# DRV8825.net
KiCad netlist of a schematic drawn in EAGLE
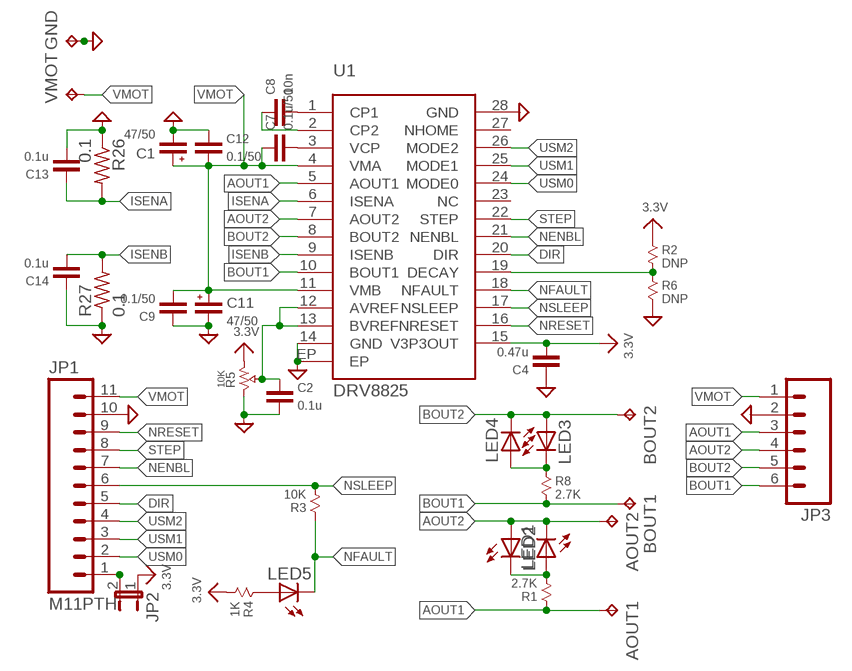
[diagram p0: schematic, sheet 1]

(export (version "E")
  (design (tool "Eeschema 10.0.6"))
  (components
    (comp (ref "AOUT1")
      (value "TPTP18R")
      (footprint "eagle-import:TP18R")
      (libsource (lib "eagle-import") (part "TPTP18R"))
    )
    (comp (ref "AOUT2")
      (value "TPTP18R")
      (footprint "eagle-import:TP18R")
      (libsource (lib "eagle-import") (part "TPTP18R"))
    )
    (comp (ref "BOUT1")
      (value "TPTP18R")
      (footprint "eagle-import:TP18R")
      (libsource (lib "eagle-import") (part "TPTP18R"))
    )
    (comp (ref "BOUT2")
      (value "TPTP18R")
      (footprint "eagle-import:TP18R")
      (libsource (lib "eagle-import") (part "TPTP18R"))
    )
    (comp (ref "C1")
      (value "47/50")
      (footprint "eagle-import:CT7343")
      (libsource (lib "eagle-import") (part "CAP-POL-7343"))
    )
    (comp (ref "C2")
      (value "0.1u")
      (footprint "eagle-import:0603")
      (libsource (lib "eagle-import") (part "CAP-0603"))
    )
    (comp (ref "C4")
      (value "0.47u")
      (footprint "eagle-import:0603")
      (libsource (lib "eagle-import") (part "CAP-0603"))
    )
    (comp (ref "C7")
      (value "0.1u/50")
      (footprint "eagle-import:0603")
      (libsource (lib "eagle-import") (part "CAP-0603"))
    )
    (comp (ref "C8")
      (value "10n")
      (footprint "eagle-import:0603")
      (libsource (lib "eagle-import") (part "CAP-0603"))
    )
    (comp (ref "C9")
      (value "0.1/50")
      (footprint "eagle-import:0603")
      (libsource (lib "eagle-import") (part "CAP-0603"))
    )
    (comp (ref "C11")
      (value "47/50")
      (footprint "eagle-import:CT7343")
      (libsource (lib "eagle-import") (part "CAP-POL-7343"))
    )
    (comp (ref "C12")
      (value "0.1/50")
      (footprint "eagle-import:0603")
      (libsource (lib "eagle-import") (part "CAP-0603"))
    )
    (comp (ref "C13")
      (value "0.1u")
      (footprint "eagle-import:0603")
      (libsource (lib "eagle-import") (part "CAP-0603"))
    )
    (comp (ref "C14")
      (value "0.1u")
      (footprint "eagle-import:0603")
      (libsource (lib "eagle-import") (part "CAP-0603"))
    )
    (comp (ref "GND")
      (value "TPTP18R")
      (footprint "eagle-import:TP18R")
      (libsource (lib "eagle-import") (part "TPTP18R"))
    )
    (comp (ref "JP1")
      (value "M11PTH")
      (footprint "eagle-import:1X11")
      (libsource (lib "eagle-import") (part "M11PTH"))
    )
    (comp (ref "JP2")
      (value "JUMPER-2SMD-NO")
      (footprint "eagle-import:SJ_2S-NO")
      (libsource (lib "eagle-import") (part "JUMPER-2SMD-NO"))
    )
    (comp (ref "JP3")
      (value "M06SIP")
      (footprint "eagle-import:1X06")
      (libsource (lib "eagle-import") (part "M06SIP"))
    )
    (comp (ref "LED1")
      (value "LEDCHIP-LED0603")
      (footprint "eagle-import:CHIP-LED0603")
      (libsource (lib "eagle-import") (part "LEDCHIP-LED0603"))
    )
    (comp (ref "LED2")
      (value "LEDCHIP-LED0603")
      (footprint "eagle-import:CHIP-LED0603")
      (libsource (lib "eagle-import") (part "LEDCHIP-LED0603"))
    )
    (comp (ref "LED3")
      (value "LEDCHIP-LED0603")
      (footprint "eagle-import:CHIP-LED0603")
      (libsource (lib "eagle-import") (part "LEDCHIP-LED0603"))
    )
    (comp (ref "LED4")
      (value "LEDCHIP-LED0603")
      (footprint "eagle-import:CHIP-LED0603")
      (libsource (lib "eagle-import") (part "LEDCHIP-LED0603"))
    )
    (comp (ref "LED5")
      (value "LEDCHIP-LED0603")
      (footprint "eagle-import:CHIP-LED0603")
      (libsource (lib "eagle-import") (part "LEDCHIP-LED0603"))
    )
    (comp (ref "R1")
      (value "2.7K")
      (footprint "eagle-import:0603")
      (libsource (lib "eagle-import") (part "RESISTOR-0603"))
    )
    (comp (ref "R2")
      (value "DNP")
      (footprint "eagle-import:0603")
      (libsource (lib "eagle-import") (part "RESISTOR-0603"))
    )
    (comp (ref "R3")
      (value "10K")
      (footprint "eagle-import:0603")
      (libsource (lib "eagle-import") (part "RESISTOR-0603"))
    )
    (comp (ref "R4")
      (value "1K")
      (footprint "eagle-import:0603")
      (libsource (lib "eagle-import") (part "RESISTOR-0603"))
    )
    (comp (ref "R5")
      (value "10K")
      (footprint "eagle-import:PVZ3A")
      (libsource (lib "eagle-import") (part "PVZ3A"))
    )
    (comp (ref "R6")
      (value "DNP")
      (footprint "eagle-import:0603")
      (libsource (lib "eagle-import") (part "RESISTOR-0603"))
    )
    (comp (ref "R8")
      (value "2.7K")
      (footprint "eagle-import:0603")
      (libsource (lib "eagle-import") (part "RESISTOR-0603"))
    )
    (comp (ref "R26")
      (value "0.1")
      (footprint "eagle-import:R2512")
      (libsource (lib "eagle-import") (part "R-US_R2512"))
    )
    (comp (ref "R27")
      (value "0.1")
      (footprint "eagle-import:R2512")
      (libsource (lib "eagle-import") (part "R-US_R2512"))
    )
    (comp (ref "U1")
      (value "DRV8825")
      (footprint "eagle-import:SSOP28EP")
      (libsource (lib "eagle-import") (part "DRV8825"))
    )
    (comp (ref "VMOT")
      (value "TPTP18R")
      (footprint "eagle-import:TP18R")
      (libsource (lib "eagle-import") (part "TPTP18R"))
    )
  )
  (nets
    (net (code "1") (name "3.3V") (class "Default")
      (node (ref "C4") (pin "1") (pinfunction "1_1") (pintype "passive"))
      (node (ref "JP2") (pin "1") (pinfunction "1_1") (pintype "passive"))
      (node (ref "R2") (pin "1") (pinfunction "1_1") (pintype "passive"))
      (node (ref "R4") (pin "2") (pinfunction "2_2") (pintype "passive"))
      (node (ref "R5") (pin "3") (pinfunction "3_3") (pintype "passive"))
      (node (ref "U1") (pin "15") (pinfunction "V3P3OUT_15") (pintype "bidirectional"))
    )
    (net (code "2") (name "AOUT1") (class "Default")
      (node (ref "AOUT1") (pin "TP") (pinfunction "TP_TP") (pintype "input"))
      (node (ref "JP3") (pin "3") (pinfunction "3_3") (pintype "passive"))
      (node (ref "R1") (pin "1") (pinfunction "1_1") (pintype "passive"))
      (node (ref "U1") (pin "5") (pinfunction "AOUT1_5") (pintype "passive"))
    )
    (net (code "3") (name "AOUT2") (class "Default")
      (node (ref "AOUT2") (pin "TP") (pinfunction "TP_TP") (pintype "input"))
      (node (ref "JP3") (pin "4") (pinfunction "4_4") (pintype "passive"))
      (node (ref "LED1") (pin "C") (pinfunction "C_C") (pintype "passive"))
      (node (ref "LED2") (pin "A") (pinfunction "A_A") (pintype "passive"))
      (node (ref "U1") (pin "7") (pinfunction "AOUT2_7") (pintype "power_in"))
    )
    (net (code "4") (name "BOUT1") (class "Default")
      (node (ref "BOUT1") (pin "TP") (pinfunction "TP_TP") (pintype "input"))
      (node (ref "JP3") (pin "6") (pinfunction "6_6") (pintype "passive"))
      (node (ref "R8") (pin "2") (pinfunction "2_2") (pintype "passive"))
      (node (ref "U1") (pin "10") (pinfunction "BOUT1_10") (pintype "passive"))
    )
    (net (code "5") (name "BOUT2") (class "Default")
      (node (ref "BOUT2") (pin "TP") (pinfunction "TP_TP") (pintype "input"))
      (node (ref "JP3") (pin "5") (pinfunction "5_5") (pintype "passive"))
      (node (ref "LED3") (pin "A") (pinfunction "A_A") (pintype "passive"))
      (node (ref "LED4") (pin "C") (pinfunction "C_C") (pintype "passive"))
      (node (ref "U1") (pin "8") (pinfunction "BOUT2_8") (pintype "passive"))
    )
    (net (code "6") (name "DIR") (class "Default")
      (node (ref "JP1") (pin "5") (pinfunction "5_5") (pintype "passive"))
      (node (ref "U1") (pin "20") (pinfunction "DIR_20") (pintype "input"))
    )
    (net (code "7") (name "GND") (class "Default")
      (node (ref "C1") (pin "-") (pinfunction "-_-") (pintype "passive"))
      (node (ref "C11") (pin "-") (pinfunction "-_-") (pintype "passive"))
      (node (ref "C12") (pin "2") (pinfunction "2_2") (pintype "passive"))
      (node (ref "C13") (pin "1") (pinfunction "1_1") (pintype "passive"))
      (node (ref "C14") (pin "2") (pinfunction "2_2") (pintype "passive"))
      (node (ref "C2") (pin "1") (pinfunction "1_1") (pintype "passive"))
      (node (ref "C4") (pin "2") (pinfunction "2_2") (pintype "passive"))
      (node (ref "C9") (pin "2") (pinfunction "2_2") (pintype "passive"))
      (node (ref "GND") (pin "TP") (pinfunction "TP_TP") (pintype "input"))
      (node (ref "JP1") (pin "10") (pinfunction "10_10") (pintype "passive"))
      (node (ref "JP3") (pin "2") (pinfunction "2_2") (pintype "passive"))
      (node (ref "R26") (pin "1") (pinfunction "1_1") (pintype "passive"))
      (node (ref "R27") (pin "1") (pinfunction "1_1") (pintype "passive"))
      (node (ref "R5") (pin "1") (pinfunction "1_1") (pintype "passive"))
      (node (ref "R6") (pin "2") (pinfunction "2_2") (pintype "passive"))
      (node (ref "U1") (pin "14") (pinfunction "GND_14") (pintype "power_in"))
      (node (ref "U1") (pin "28") (pinfunction "GND_28") (pintype "power_in"))
      (node (ref "U1") (pin "EP") (pinfunction "EP_EP") (pintype "power_in"))
    )
    (net (code "8") (name "ISENA") (class "Default")
      (node (ref "C13") (pin "2") (pinfunction "2_2") (pintype "passive"))
      (node (ref "R26") (pin "2") (pinfunction "2_2") (pintype "passive"))
      (node (ref "U1") (pin "6") (pinfunction "ISENA_6") (pintype "passive"))
    )
    (net (code "9") (name "ISENB") (class "Default")
      (node (ref "C14") (pin "1") (pinfunction "1_1") (pintype "passive"))
      (node (ref "R27") (pin "2") (pinfunction "2_2") (pintype "passive"))
      (node (ref "U1") (pin "9") (pinfunction "ISENB_9") (pintype "passive"))
    )
    (net (code "10") (name "NENBL") (class "Default")
      (node (ref "JP1") (pin "7") (pinfunction "7_7") (pintype "passive"))
      (node (ref "U1") (pin "21") (pinfunction "NENBL_21") (pintype "input"))
    )
    (net (code "11") (name "NFAULT") (class "Default")
      (node (ref "LED5") (pin "C") (pinfunction "C_C") (pintype "passive"))
      (node (ref "R3") (pin "1") (pinfunction "1_1") (pintype "passive"))
      (node (ref "U1") (pin "18") (pinfunction "NFAULT_18") (pintype "open_collector"))
    )
    (net (code "12") (name "NRESET") (class "Default")
      (node (ref "JP1") (pin "9") (pinfunction "9_9") (pintype "passive"))
      (node (ref "U1") (pin "16") (pinfunction "NRESET_16") (pintype "input"))
    )
    (net (code "13") (name "NSLEEP") (class "Default")
      (node (ref "JP1") (pin "6") (pinfunction "6_6") (pintype "passive"))
      (node (ref "R3") (pin "2") (pinfunction "2_2") (pintype "passive"))
      (node (ref "U1") (pin "17") (pinfunction "NSLEEP_17") (pintype "input"))
    )
    (net (code "14") (name "Net-(JP1-Pad1)") (class "Default")
      (node (ref "JP1") (pin "1") (pinfunction "1_1") (pintype "passive"))
      (node (ref "JP2") (pin "2") (pinfunction "2_2") (pintype "passive"))
    )
    (net (code "15") (name "Net-(LED1-PadA)") (class "Default")
      (node (ref "LED1") (pin "A") (pinfunction "A_A") (pintype "passive"))
      (node (ref "LED2") (pin "C") (pinfunction "C_C") (pintype "passive"))
      (node (ref "R1") (pin "2") (pinfunction "2_2") (pintype "passive"))
    )
    (net (code "16") (name "Net-(LED3-PadC)") (class "Default")
      (node (ref "LED3") (pin "C") (pinfunction "C_C") (pintype "passive"))
      (node (ref "LED4") (pin "A") (pinfunction "A_A") (pintype "passive"))
      (node (ref "R8") (pin "1") (pinfunction "1_1") (pintype "passive"))
    )
    (net (code "17") (name "Net-(LED5-PadA)") (class "Default")
      (node (ref "LED5") (pin "A") (pinfunction "A_A") (pintype "passive"))
      (node (ref "R4") (pin "1") (pinfunction "1_1") (pintype "passive"))
    )
    (net (code "18") (name "Net-(U1-AVREF)") (class "Default")
      (node (ref "C2") (pin "2") (pinfunction "2_2") (pintype "passive"))
      (node (ref "R5") (pin "2") (pinfunction "2_2") (pintype "passive"))
      (node (ref "U1") (pin "12") (pinfunction "AVREF_12") (pintype "passive"))
      (node (ref "U1") (pin "13") (pinfunction "BVREF_13") (pintype "passive"))
    )
    (net (code "19") (name "Net-(U1-CP1)") (class "Default")
      (node (ref "C8") (pin "1") (pinfunction "1_1") (pintype "passive"))
      (node (ref "U1") (pin "1") (pinfunction "CP1_1") (pintype "passive"))
    )
    (net (code "20") (name "Net-(U1-CP2)") (class "Default")
      (node (ref "C8") (pin "2") (pinfunction "2_2") (pintype "passive"))
      (node (ref "U1") (pin "2") (pinfunction "CP2_2") (pintype "passive"))
    )
    (net (code "21") (name "Net-(U1-DECAY)") (class "Default")
      (node (ref "R2") (pin "2") (pinfunction "2_2") (pintype "passive"))
      (node (ref "R6") (pin "1") (pinfunction "1_1") (pintype "passive"))
      (node (ref "U1") (pin "19") (pinfunction "DECAY_19") (pintype "input"))
    )
    (net (code "22") (name "Net-(U1-VCP)") (class "Default")
      (node (ref "C7") (pin "1") (pinfunction "1_1") (pintype "passive"))
      (node (ref "U1") (pin "3") (pinfunction "VCP_3") (pintype "passive"))
    )
    (net (code "23") (name "STEP") (class "Default")
      (node (ref "JP1") (pin "8") (pinfunction "8_8") (pintype "passive"))
      (node (ref "U1") (pin "22") (pinfunction "STEP_22") (pintype "input"))
    )
    (net (code "24") (name "USM0") (class "Default")
      (node (ref "JP1") (pin "2") (pinfunction "2_2") (pintype "passive"))
      (node (ref "U1") (pin "24") (pinfunction "MODE0_24") (pintype "input"))
    )
    (net (code "25") (name "USM1") (class "Default")
      (node (ref "JP1") (pin "3") (pinfunction "3_3") (pintype "passive"))
      (node (ref "U1") (pin "25") (pinfunction "MODE1_25") (pintype "input"))
    )
    (net (code "26") (name "USM2") (class "Default")
      (node (ref "JP1") (pin "4") (pinfunction "4_4") (pintype "passive"))
      (node (ref "U1") (pin "26") (pinfunction "MODE2_26") (pintype "input"))
    )
    (net (code "27") (name "VMOT") (class "Default")
      (node (ref "C1") (pin "+") (pinfunction "+_+") (pintype "passive"))
      (node (ref "C11") (pin "+") (pinfunction "+_+") (pintype "passive"))
      (node (ref "C12") (pin "1") (pinfunction "1_1") (pintype "passive"))
      (node (ref "C7") (pin "2") (pinfunction "2_2") (pintype "passive"))
      (node (ref "C9") (pin "1") (pinfunction "1_1") (pintype "passive"))
      (node (ref "JP1") (pin "11") (pinfunction "11_11") (pintype "passive"))
      (node (ref "JP3") (pin "1") (pinfunction "1_1") (pintype "passive"))
      (node (ref "U1") (pin "11") (pinfunction "VMB_11") (pintype "passive"))
      (node (ref "U1") (pin "4") (pinfunction "VMA_4") (pintype "passive"))
      (node (ref "VMOT") (pin "TP") (pinfunction "TP_TP") (pintype "input"))
    )
    (net (code "28") (name "unconnected-(U1-NC-Pad23)") (class "Default")
      (node (ref "U1") (pin "23") (pinfunction "NC_23") (pintype "no_connect"))
    )
    (net (code "29") (name "unconnected-(U1-NHOME-Pad27)") (class "Default")
      (node (ref "U1") (pin "27") (pinfunction "NHOME_27") (pintype "open_collector"))
    )
  )
)
